# Tiny_5_Circle_PTH_-v3.net
KiCad netlist of a schematic drawn in EAGLE
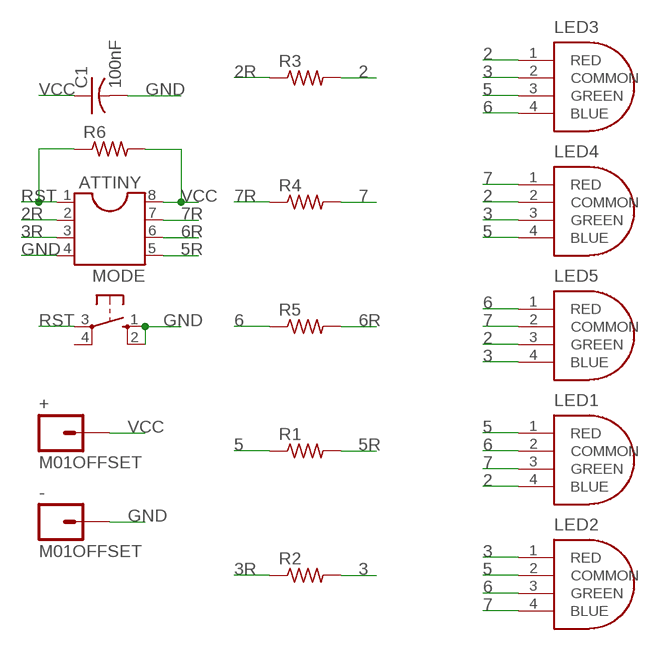
[diagram p0: schematic, sheet 1]

(export (version "E")
  (design (tool "Eeschema 10.0.6"))
  (components
    (comp (ref "+")
      (value "M01OFFSET")
      (footprint "eagle-import:1X01_OFFSET")
      (libsource (lib "eagle-import") (part "M01OFFSET"))
    )
    (comp (ref "-")
      (value "M01OFFSET")
      (footprint "eagle-import:1X01_OFFSET")
      (libsource (lib "eagle-import") (part "M01OFFSET"))
    )
    (comp (ref "ATTINY")
      (value "DIL8S")
      (footprint "eagle-import:SOCKET-08")
      (libsource (lib "eagle-import") (part "DIL8S"))
    )
    (comp (ref "C1")
      (value "100nF")
      (footprint "eagle-import:C025-025X050")
      (libsource (lib "eagle-import") (part "C-US025-025X050"))
    )
    (comp (ref "LED1")
      (value "10MM-RGB-LEDACTIVELYUSED")
      (footprint "eagle-import:10MM-RGB-LED-IN-USE")
      (libsource (lib "eagle-import") (part "10MM-RGB-LEDACTIVELYUSED"))
    )
    (comp (ref "LED2")
      (value "10MM-RGB-LEDACTIVELYUSED")
      (footprint "eagle-import:10MM-RGB-LED-IN-USE")
      (libsource (lib "eagle-import") (part "10MM-RGB-LEDACTIVELYUSED"))
    )
    (comp (ref "LED3")
      (value "10MM-RGB-LEDACTIVELYUSED")
      (footprint "eagle-import:10MM-RGB-LED-IN-USE")
      (libsource (lib "eagle-import") (part "10MM-RGB-LEDACTIVELYUSED"))
    )
    (comp (ref "LED4")
      (value "10MM-RGB-LEDACTIVELYUSED")
      (footprint "eagle-import:10MM-RGB-LED-IN-USE")
      (libsource (lib "eagle-import") (part "10MM-RGB-LEDACTIVELYUSED"))
    )
    (comp (ref "LED5")
      (value "10MM-RGB-LEDACTIVELYUSED")
      (footprint "eagle-import:10MM-RGB-LED-IN-USE")
      (libsource (lib "eagle-import") (part "10MM-RGB-LEDACTIVELYUSED"))
    )
    (comp (ref "MODE")
      (value "10-XX")
      (footprint "eagle-import:B3F-10XX")
      (fields (field (name "MPN") "B3F-1000"))
      (libsource (lib "eagle-import") (part "10-XX"))
    )
    (comp (ref "R1")
      (value "R-US_0207/7")
      (footprint "eagle-import:0207_7")
      (libsource (lib "eagle-import") (part "R-US_0207/7"))
    )
    (comp (ref "R2")
      (value "R-US_0207/7")
      (footprint "eagle-import:0207_7")
      (libsource (lib "eagle-import") (part "R-US_0207/7"))
    )
    (comp (ref "R3")
      (value "R-US_0207/7")
      (footprint "eagle-import:0207_7")
      (libsource (lib "eagle-import") (part "R-US_0207/7"))
    )
    (comp (ref "R4")
      (value "R-US_0207/7")
      (footprint "eagle-import:0207_7")
      (libsource (lib "eagle-import") (part "R-US_0207/7"))
    )
    (comp (ref "R5")
      (value "R-US_0207/7")
      (footprint "eagle-import:0207_7")
      (libsource (lib "eagle-import") (part "R-US_0207/7"))
    )
    (comp (ref "R6")
      (value "R-US_0207/2V")
      (footprint "eagle-import:0207_2V")
      (libsource (lib "eagle-import") (part "R-US_0207/2V"))
    )
  )
  (nets
    (net (code "1") (name "/2") (class "Default")
      (node (ref "LED1") (pin "4") (pinfunction "BLUE_4") (pintype "bidirectional"))
      (node (ref "LED3") (pin "1") (pinfunction "RED_1") (pintype "bidirectional"))
      (node (ref "LED4") (pin "2") (pinfunction "COMMON_2") (pintype "bidirectional"))
      (node (ref "LED5") (pin "3") (pinfunction "GREEN_3") (pintype "bidirectional"))
      (node (ref "R3") (pin "2") (pinfunction "2_2") (pintype "passive"))
    )
    (net (code "2") (name "/2R") (class "Default")
      (node (ref "ATTINY") (pin "2") (pinfunction "2_2") (pintype "passive"))
      (node (ref "R3") (pin "1") (pinfunction "1_1") (pintype "passive"))
    )
    (net (code "3") (name "/3") (class "Default")
      (node (ref "LED2") (pin "1") (pinfunction "RED_1") (pintype "bidirectional"))
      (node (ref "LED3") (pin "2") (pinfunction "COMMON_2") (pintype "bidirectional"))
      (node (ref "LED4") (pin "3") (pinfunction "GREEN_3") (pintype "bidirectional"))
      (node (ref "LED5") (pin "4") (pinfunction "BLUE_4") (pintype "bidirectional"))
      (node (ref "R2") (pin "2") (pinfunction "2_2") (pintype "passive"))
    )
    (net (code "4") (name "/3R") (class "Default")
      (node (ref "ATTINY") (pin "3") (pinfunction "3_3") (pintype "passive"))
      (node (ref "R2") (pin "1") (pinfunction "1_1") (pintype "passive"))
    )
    (net (code "5") (name "/5") (class "Default")
      (node (ref "LED1") (pin "1") (pinfunction "RED_1") (pintype "bidirectional"))
      (node (ref "LED2") (pin "2") (pinfunction "COMMON_2") (pintype "bidirectional"))
      (node (ref "LED3") (pin "3") (pinfunction "GREEN_3") (pintype "bidirectional"))
      (node (ref "LED4") (pin "4") (pinfunction "BLUE_4") (pintype "bidirectional"))
      (node (ref "R1") (pin "1") (pinfunction "1_1") (pintype "passive"))
    )
    (net (code "6") (name "/5R") (class "Default")
      (node (ref "ATTINY") (pin "5") (pinfunction "5_5") (pintype "passive"))
      (node (ref "R1") (pin "2") (pinfunction "2_2") (pintype "passive"))
    )
    (net (code "7") (name "/6") (class "Default")
      (node (ref "LED1") (pin "2") (pinfunction "COMMON_2") (pintype "bidirectional"))
      (node (ref "LED2") (pin "3") (pinfunction "GREEN_3") (pintype "bidirectional"))
      (node (ref "LED3") (pin "4") (pinfunction "BLUE_4") (pintype "bidirectional"))
      (node (ref "LED5") (pin "1") (pinfunction "RED_1") (pintype "bidirectional"))
      (node (ref "R5") (pin "1") (pinfunction "1_1") (pintype "passive"))
    )
    (net (code "8") (name "/6R") (class "Default")
      (node (ref "ATTINY") (pin "6") (pinfunction "6_6") (pintype "passive"))
      (node (ref "R5") (pin "2") (pinfunction "2_2") (pintype "passive"))
    )
    (net (code "9") (name "/7") (class "Default")
      (node (ref "LED1") (pin "3") (pinfunction "GREEN_3") (pintype "bidirectional"))
      (node (ref "LED2") (pin "4") (pinfunction "BLUE_4") (pintype "bidirectional"))
      (node (ref "LED4") (pin "1") (pinfunction "RED_1") (pintype "bidirectional"))
      (node (ref "LED5") (pin "2") (pinfunction "COMMON_2") (pintype "bidirectional"))
      (node (ref "R4") (pin "2") (pinfunction "2_2") (pintype "passive"))
    )
    (net (code "10") (name "/7R") (class "Default")
      (node (ref "ATTINY") (pin "7") (pinfunction "7_7") (pintype "passive"))
      (node (ref "R4") (pin "1") (pinfunction "1_1") (pintype "passive"))
    )
    (net (code "11") (name "/GND") (class "Default")
      (node (ref "-") (pin "1") (pinfunction "1_1") (pintype "passive"))
      (node (ref "ATTINY") (pin "4") (pinfunction "4_4") (pintype "passive"))
      (node (ref "C1") (pin "2") (pinfunction "2_2") (pintype "passive"))
      (node (ref "MODE") (pin "1") (pinfunction "S_1") (pintype "passive"))
      (node (ref "MODE") (pin "2") (pinfunction "S1_2") (pintype "passive"))
    )
    (net (code "12") (name "/RST") (class "Default")
      (node (ref "ATTINY") (pin "1") (pinfunction "1_1") (pintype "passive"))
      (node (ref "MODE") (pin "3") (pinfunction "P_3") (pintype "passive"))
      (node (ref "R6") (pin "1") (pinfunction "1_1") (pintype "passive"))
    )
    (net (code "13") (name "/VCC") (class "Default")
      (node (ref "+") (pin "1") (pinfunction "1_1") (pintype "passive"))
      (node (ref "ATTINY") (pin "8") (pinfunction "8_8") (pintype "passive"))
      (node (ref "C1") (pin "1") (pinfunction "1_1") (pintype "passive"))
      (node (ref "R6") (pin "2") (pinfunction "2_2") (pintype "passive"))
    )
    (net (code "14") (name "unconnected-(MODE-P1-Pad4)") (class "Default")
      (node (ref "MODE") (pin "4") (pinfunction "P1_4") (pintype "passive"))
    )
  )
)
